# 26_RS485.net
KiCad netlist of a schematic drawn in Altium Designer
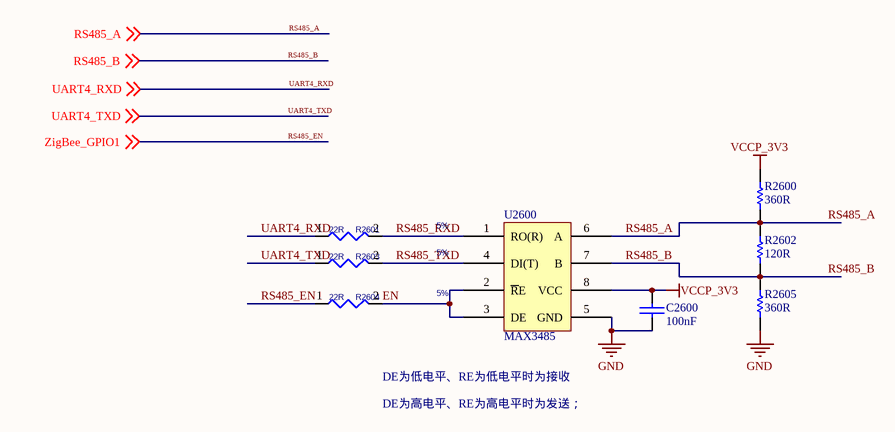
[diagram p0: 26_RS485.SchDoc]

(export (version "E")
  (design (tool "Eeschema 10.0.6"))
  (components
    (comp (ref "C2600")
      (value "100nF")
      (footprint "C0402")
      (description "无极性电容")
      (libsource (lib "电容") (part "CAP"))
    )
    (comp (ref "R2600") (value "360R") (footprint "R0402") (libsource (lib "电阻") (part "RES")))
    (comp (ref "R2601")
      (value "22R")
      (footprint "R0402")
      (description "通用厚膜电阻,22R,+/-5%,R0402,1/16W.")
      (fields
        (field (name "TOLERANCE") "5%")
        (field (name "MANUFACTURER") "YAGEO")
        (field (name "CREATED BY") "YTL")
      )
      (libsource (lib "*") (part "RESISTOR_Dup1"))
    )
    (comp (ref "R2602") (value "120R") (footprint "R0402") (libsource (lib "电阻") (part "RES")))
    (comp (ref "R2603")
      (value "22R")
      (footprint "R0402")
      (description "通用厚膜电阻,22R,+/-5%,R0402,1/16W.")
      (fields
        (field (name "TOLERANCE") "5%")
        (field (name "MANUFACTURER") "YAGEO")
        (field (name "CREATED BY") "YTL")
      )
      (libsource (lib "*") (part "RESISTOR_Dup1"))
    )
    (comp (ref "R2604")
      (value "22R")
      (footprint "R0402")
      (description "通用厚膜电阻,22R,+/-5%,R0402,1/16W.")
      (fields
        (field (name "TOLERANCE") "5%")
        (field (name "MANUFACTURER") "YAGEO")
        (field (name "CREATED BY") "YTL")
      )
      (libsource (lib "*") (part "RESISTOR_Dup1"))
    )
    (comp (ref "R2605") (value "360R") (footprint "R0402") (libsource (lib "电阻") (part "RES")))
    (comp (ref "U2600") (value "MAX3485") (footprint "MSOP-8") (libsource (lib "my_Library") (part "MAX485")))
  )
  (nets
    (net (code "1") (name "/EN") (class "Default")
      (node (ref "R2604") (pin "2") (pinfunction "2_2") (pintype "passive"))
      (node (ref "U2600") (pin "2") (pinfunction "~{R}E_2") (pintype "passive"))
      (node (ref "U2600") (pin "3") (pinfunction "DE_3") (pintype "passive"))
    )
    (net (code "2") (name "/RS485_RXD") (class "Default")
      (node (ref "R2601") (pin "2") (pinfunction "2_2") (pintype "passive"))
      (node (ref "U2600") (pin "1") (pinfunction "RO(R)_1") (pintype "passive"))
    )
    (net (code "3") (name "/RS485_TXD") (class "Default")
      (node (ref "R2603") (pin "2") (pinfunction "2_2") (pintype "passive"))
      (node (ref "U2600") (pin "4") (pinfunction "DI(T)_4") (pintype "passive"))
    )
    (net (code "4") (name "GND") (class "Default")
      (node (ref "C2600") (pin "1") (pinfunction "1_1") (pintype "passive"))
      (node (ref "R2605") (pin "1") (pinfunction "1_1") (pintype "passive"))
      (node (ref "U2600") (pin "5") (pinfunction "GND_5") (pintype "passive"))
    )
    (net (code "5") (name "RS485_A") (class "Default")
      (node (ref "R2600") (pin "1") (pinfunction "1_1") (pintype "passive"))
      (node (ref "R2602") (pin "2") (pinfunction "2_2") (pintype "passive"))
      (node (ref "U2600") (pin "6") (pinfunction "A_6") (pintype "passive"))
    )
    (net (code "6") (name "RS485_B") (class "Default")
      (node (ref "R2602") (pin "1") (pinfunction "1_1") (pintype "passive"))
      (node (ref "R2605") (pin "2") (pinfunction "2_2") (pintype "passive"))
      (node (ref "U2600") (pin "7") (pinfunction "B_7") (pintype "passive"))
    )
    (net (code "7") (name "UART4_RXD") (class "Default")
      (node (ref "R2601") (pin "1") (pinfunction "1_1") (pintype "passive"))
    )
    (net (code "8") (name "UART4_TXD") (class "Default")
      (node (ref "R2603") (pin "1") (pinfunction "1_1") (pintype "passive"))
    )
    (net (code "9") (name "VCCP_3V3") (class "Default")
      (node (ref "C2600") (pin "2") (pinfunction "2_2") (pintype "passive"))
      (node (ref "R2600") (pin "2") (pinfunction "2_2") (pintype "passive"))
      (node (ref "U2600") (pin "8") (pinfunction "VCC_8") (pintype "passive"))
    )
    (net (code "10") (name "ZigBee_GPIO1") (class "Default")
      (node (ref "R2604") (pin "1") (pinfunction "1_1") (pintype "passive"))
    )
  )
)
